# 5V_3A.net
KiCad netlist of a schematic drawn in Altium Designer
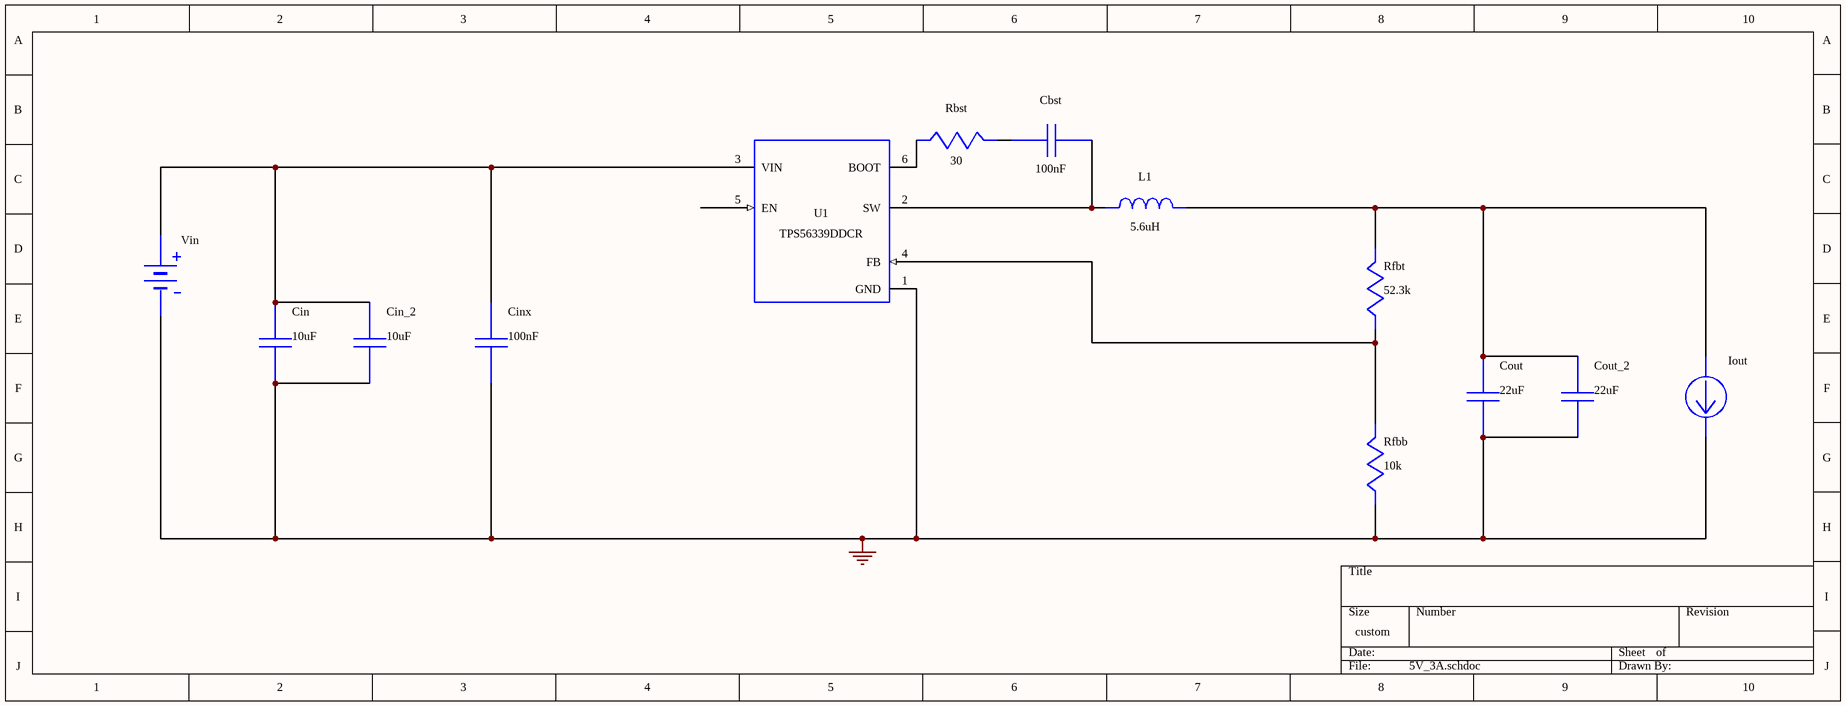
[diagram p0: 5V_3A.schdoc]

(export (version "E")
  (design (tool "Eeschema 10.0.6"))
  (components
    (comp (ref "Cbst")
      (value "100nF")
      (description "C0805C104M5RACTU")
      (libsource (lib "TI WEBENCH") (part "Cbst"))
    )
    (comp (ref "Cin")
      (value "10uF")
      (description "GRM21BR61E106MA7")
      (fields (field (name "MANUFACTURER PART NUMBER") "GRM21BR61E106MA73L"))
      (libsource (lib "TI WEBENCH") (part "Cin"))
    )
    (comp (ref "Cinx")
      (value "100nF")
      (description "C0805C104M5RACTU")
      (libsource (lib "TI WEBENCH") (part "Cinx"))
    )
    (comp (ref "Cin_2")
      (value "10uF")
      (description "GRM21BR61E106MA7")
      (fields (field (name "MANUFACTURER PART NUMBER") "GRM21BR61E106MA73L"))
      (libsource (lib "TI WEBENCH") (part "Cin_2"))
    )
    (comp (ref "Cout")
      (value "22uF")
      (description "C2012X7S1A226M12")
      (fields (field (name "MANUFACTURER PART NUMBER") "C2012X7S1A226M125AC"))
      (libsource (lib "TI WEBENCH") (part "Cout"))
    )
    (comp (ref "Cout_2")
      (value "22uF")
      (description "C2012X7S1A226M12")
      (fields (field (name "MANUFACTURER PART NUMBER") "C2012X7S1A226M125AC"))
      (libsource (lib "TI WEBENCH") (part "Cout_2"))
    )
    (comp (ref "Iout") (value "WB_CURRENT_LOAD") (libsource (lib "TI WEBENCH") (part "Iout")))
    (comp (ref "L1")
      (value "5.6uH")
      (description "Unknown")
      (fields (field (name "MANUFACTURER PART NUMBER") "SRP6540-5R6M"))
      (libsource (lib "TI WEBENCH") (part "L1"))
    )
    (comp (ref "Rbst")
      (value "30")
      (description "RC0603FR-0730RL")
      (libsource (lib "TI WEBENCH") (part "Rbst"))
    )
    (comp (ref "Rfbb")
      (value "10k")
      (description "CRCW060310K0FKEA")
      (libsource (lib "TI WEBENCH") (part "Rfbb"))
    )
    (comp (ref "Rfbt")
      (value "52.3k")
      (description "CRCW060352K3FKEA")
      (libsource (lib "TI WEBENCH") (part "Rfbt"))
    )
    (comp (ref "U1")
      (value "TPS56339DDCR")
      (fields (field (name "PACKAGEREFERENCE") "TPS56339DDCR"))
      (libsource (lib "TI WEBENCH") (part "U1"))
    )
    (comp (ref "Vin") (value "WB_BATTERY") (libsource (lib "TI WEBENCH") (part "Vin")))
  )
  (nets
    (net (code "1") (name "0") (class "Default")
      (node (ref "Cin") (pin "2") (pinfunction "2_2") (pintype "passive"))
      (node (ref "Cin_2") (pin "2") (pinfunction "2_2") (pintype "passive"))
      (node (ref "Cinx") (pin "2") (pinfunction "2_2") (pintype "passive"))
      (node (ref "Cout") (pin "2") (pinfunction "2_2") (pintype "passive"))
      (node (ref "Cout_2") (pin "2") (pinfunction "2_2") (pintype "passive"))
      (node (ref "Iout") (pin "2") (pinfunction "-_2") (pintype "passive"))
      (node (ref "Rfbb") (pin "2") (pinfunction "2_2") (pintype "passive"))
      (node (ref "U1") (pin "1") (pinfunction "GND_1") (pintype "power_in"))
      (node (ref "Vin") (pin "2") (pinfunction "-_2") (pintype "passive"))
    )
    (net (code "2") (name "Net-(Cbst-Pad1)") (class "Default")
      (node (ref "Cbst") (pin "1") (pinfunction "1_1") (pintype "passive"))
      (node (ref "Rbst") (pin "1") (pinfunction "1_1") (pintype "passive"))
    )
    (net (code "3") (name "Net-(Iout-+)") (class "Default")
      (node (ref "Cout") (pin "1") (pinfunction "1_1") (pintype "passive"))
      (node (ref "Cout_2") (pin "1") (pinfunction "1_1") (pintype "passive"))
      (node (ref "Iout") (pin "1") (pinfunction "+_1") (pintype "passive"))
      (node (ref "L1") (pin "1") (pinfunction "1_1") (pintype "passive"))
      (node (ref "Rfbt") (pin "1") (pinfunction "1_1") (pintype "passive"))
    )
    (net (code "4") (name "Net-(U1-BOOT)") (class "Default")
      (node (ref "Rbst") (pin "2") (pinfunction "2_2") (pintype "passive"))
      (node (ref "U1") (pin "6") (pinfunction "BOOT_6") (pintype "power_in"))
    )
    (net (code "5") (name "Net-(U1-FB)") (class "Default")
      (node (ref "Rfbb") (pin "1") (pinfunction "1_1") (pintype "passive"))
      (node (ref "Rfbt") (pin "2") (pinfunction "2_2") (pintype "passive"))
      (node (ref "U1") (pin "4") (pinfunction "FB_4") (pintype "input"))
    )
    (net (code "6") (name "Net-(U1-SW)") (class "Default")
      (node (ref "Cbst") (pin "2") (pinfunction "2_2") (pintype "passive"))
      (node (ref "L1") (pin "2") (pinfunction "2_2") (pintype "passive"))
      (node (ref "U1") (pin "2") (pinfunction "SW_2") (pintype "power_in"))
    )
    (net (code "7") (name "Net-(U1-VIN)") (class "Default")
      (node (ref "Cin") (pin "1") (pinfunction "1_1") (pintype "passive"))
      (node (ref "Cin_2") (pin "1") (pinfunction "1_1") (pintype "passive"))
      (node (ref "Cinx") (pin "1") (pinfunction "1_1") (pintype "passive"))
      (node (ref "U1") (pin "3") (pinfunction "VIN_3") (pintype "power_in"))
      (node (ref "Vin") (pin "1") (pinfunction "+_1") (pintype "passive"))
    )
    (net (code "8") (name "unconnected-(U1-EN-Pad5)") (class "Default")
      (node (ref "U1") (pin "5") (pinfunction "EN_5") (pintype "input"))
    )
  )
)
